# DEMO_Bus_Panel.net
KiCad netlist of a schematic drawn in EAGLE
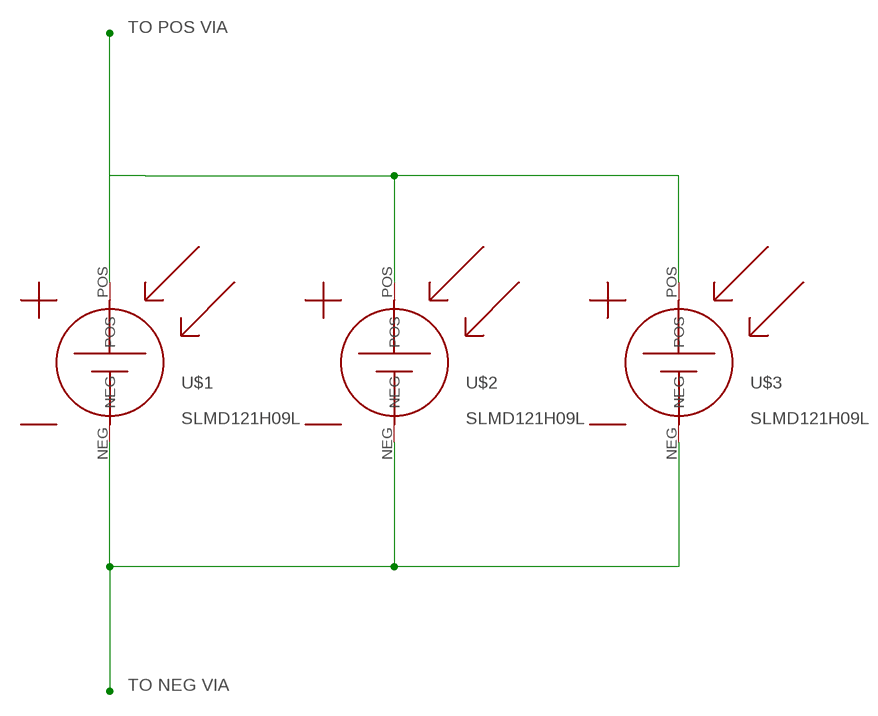
[diagram p0: schematic, sheet 1]

(export (version "E")
  (design (tool "Eeschema 10.0.6"))
  (components
    (comp (ref "U$1")
      (value "SLMD121H09L")
      (footprint "eagle-import:MONO_SOLAR_CELL_62X21")
      (libsource (lib "eagle-import") (part "SLMD121H09L"))
    )
    (comp (ref "U$2")
      (value "SLMD121H09L")
      (footprint "eagle-import:MONO_SOLAR_CELL_62X21")
      (libsource (lib "eagle-import") (part "SLMD121H09L"))
    )
    (comp (ref "U$3")
      (value "SLMD121H09L")
      (footprint "eagle-import:MONO_SOLAR_CELL_62X21")
      (libsource (lib "eagle-import") (part "SLMD121H09L"))
    )
  )
  (nets
    (net (code "1") (name "Net-(U$1-PadNEG)") (class "Default")
      (node (ref "U$1") (pin "NEG") (pinfunction "NEG_NEG") (pintype "bidirectional"))
      (node (ref "U$2") (pin "NEG") (pinfunction "NEG_NEG") (pintype "bidirectional"))
      (node (ref "U$3") (pin "NEG") (pinfunction "NEG_NEG") (pintype "bidirectional"))
    )
    (net (code "2") (name "Net-(U$1-PadPOS)") (class "Default")
      (node (ref "U$1") (pin "POS") (pinfunction "POS_POS") (pintype "bidirectional"))
      (node (ref "U$2") (pin "POS") (pinfunction "POS_POS") (pintype "bidirectional"))
      (node (ref "U$3") (pin "POS") (pinfunction "POS_POS") (pintype "bidirectional"))
    )
  )
)
